# AFE_Channel_2.net
KiCad netlist of a schematic drawn in Altium Designer
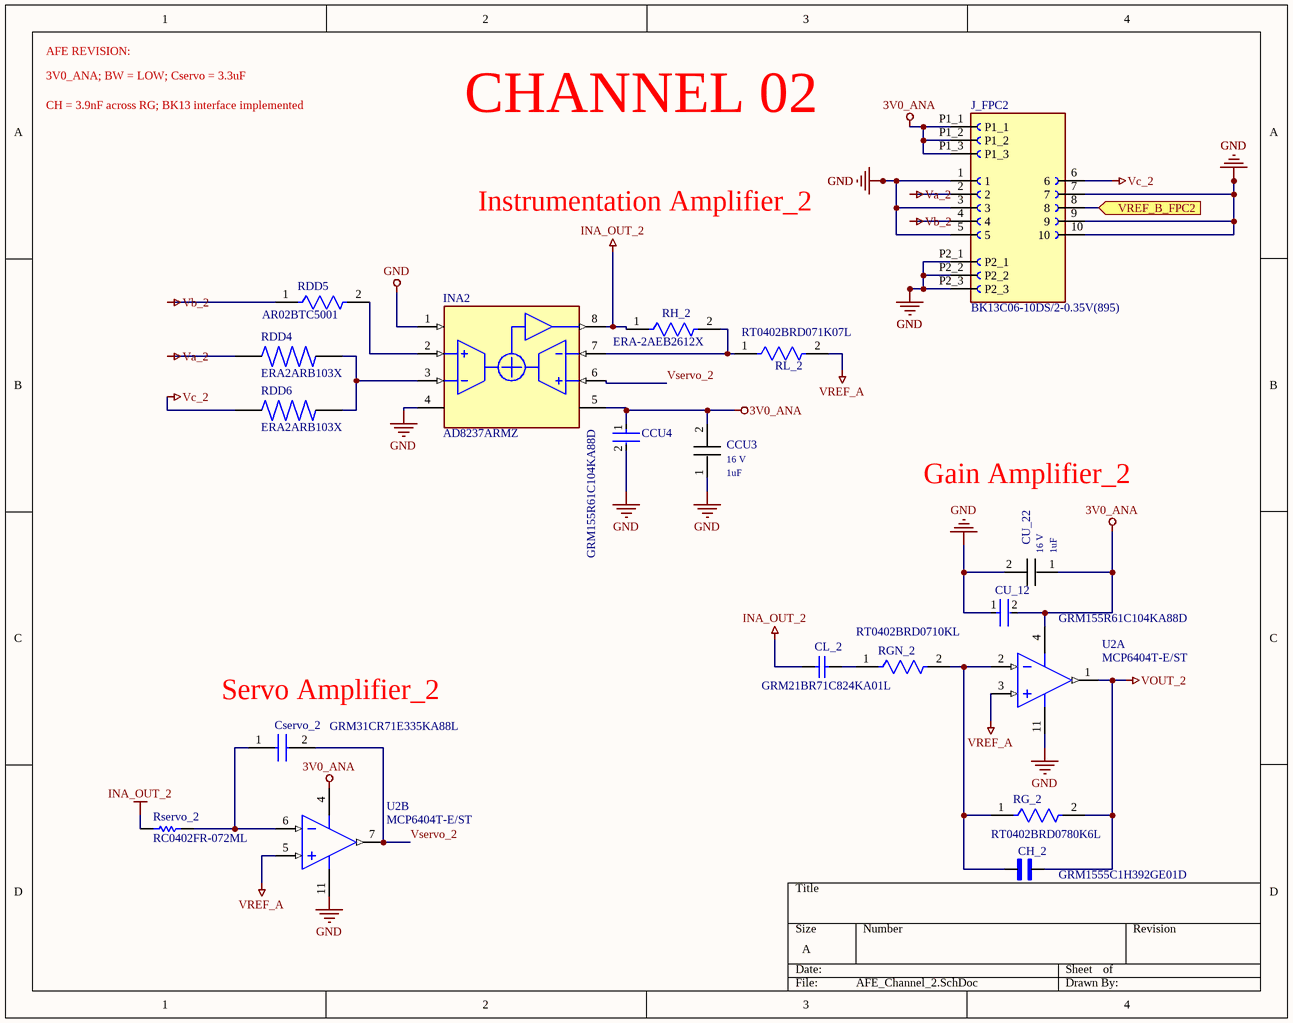
[diagram p0: AFE_Channel_2.SchDoc]

(export (version "E")
  (design (tool "Eeschema 10.0.6"))
  (components
    (comp (ref "CCU3")
      (value "MURATA_GRM155C71C105KE11D")
      (footprint "MURATA_GRM155C71C105KE11D_0:*MURATA_GRM155C71C105KE11D_0")
      (description "Murata GRM155C71C105KE11D: 1 uF 16 V X7S +/-10%, 0402/1005 metric")
      (fields (field (name "MF") "Murata") (field (name "MP") "GRM155C71C105KE11D"))
      (libsource (lib "EMG_Controlled_R5") (part "EMG_R5_CCU3"))
    )
    (comp (ref "CCU4")
      (value "GRM155R61C104KA88D")
      (footprint "96DF66F8-B997-472F-A885-42BCAAE661B2_FP-GRM155-0_05-IPC_C:FP-GRM155-0_05-IPC_C")
      (description "CAP CER 0.1UF 16V X5R 0402")
      (fields (field (name "VOLTAGE") "16V") (field (name "TOLERANCE") "10%"))
      (libsource (lib "EMG_Controlled_R5") (part "EMG_R5_CCU4"))
    )
    (comp (ref "CH_2")
      (value "GRM1555C1H392GE01D")
      (footprint "GRM1555C1H392GE01D_0:CAPC1005X55N")
      (description "SMD capacitor C0G(EIA) with capacitance 3900pF Tol.2%. Rated voltage 50Vdc 125C")
      (fields (field (name "MF") "Murata Electronics"))
      (libsource (lib "EMG_Controlled_R5") (part "EMG_R5_CH_2"))
    )
    (comp (ref "CL_2")
      (value "GRM21BR71C824KA01L")
      (footprint "987105EF-01FA-4198-A59F-44D3B68BB40E_CAPC2013X135X45ML10T25:CAPC2013X135X45ML10T25")
      (fields (field (name "MANUFACTURER") "Murata"))
      (libsource (lib "EMG_Controlled_R5") (part "EMG_R5_CL_2"))
    )
    (comp (ref "Cservo_2")
      (value "GRM31CR71E335KA88L")
      (footprint "SamacSys:GRM31x")
      (description "Capacitor")
      (fields
        (field (name "MOUSER PART NUMBER") "81-GRM31CR71E335KA8L")
        (field (name "MANUFACTURER") "Murata")
      )
      (libsource (lib "EMG_Controlled_R5") (part "EMG_R5_Cservo_2"))
    )
    (comp (ref "CU_12")
      (value "GRM155R61C104KA88D")
      (footprint "96DF66F8-B997-472F-A885-42BCAAE661B2_FP-GRM155-0_05-IPC_C:FP-GRM155-0_05-IPC_C")
      (description "CAP CER 0.1UF 16V X5R 0402")
      (fields (field (name "VOLTAGE") "16V") (field (name "TOLERANCE") "10%"))
      (libsource (lib "EMG_Controlled_R5") (part "EMG_R5_CU_12"))
    )
    (comp (ref "CU_22")
      (value "MURATA_GRM155C71C105KE11D")
      (footprint "MURATA_GRM155C71C105KE11D_0:*MURATA_GRM155C71C105KE11D_0")
      (description "Murata GRM155C71C105KE11D: 1 uF 16 V X7S +/-10%, 0402/1005 metric")
      (fields (field (name "MF") "Murata") (field (name "MP") "GRM155C71C105KE11D"))
      (libsource (lib "EMG_Controlled_R5") (part "EMG_R5_CU_22"))
    )
    (comp (ref "INA2")
      (value "AD8237ARMZ")
      (footprint "EMG_AD8237_R3:EMG_AD8237_R3_MSOP8")
      (description "Micropower, Zero Drift, True Rail-to-Rail Instrumentation Amplifier")
      (fields (field (name "MF") "Analog Devices"))
      (libsource (lib "EMG_Controlled_R5") (part "EMG_R5_INA2"))
    )
    (comp (ref "J_FPC2")
      (value "BK13C06-10DS/2-0.35V(895)")
      (footprint "BK13C06-10DS_2-0.35V_895__0:HIROSE_BK13C06-10DS/2-0.35V(895)")
      (description "10 Position Connector Receptacle, Center Strip Contacts Surface Mount Gold")
      (fields (field (name "MF") "Hirose Electric Co Ltd"))
      (libsource (lib "EMG_Controlled_R5") (part "EMG_R5_J_FPC2"))
    )
    (comp (ref "RDD4")
      (value "ERA2ARB103X")
      (footprint "ERA2ARB103X_0:RES_ERA2ARB103X")
      (libsource (lib "EMG_Controlled_R5") (part "EMG_R5_RDD4"))
    )
    (comp (ref "RDD5")
      (value "AR02BTC5001")
      (footprint "7D606042-220B-45EE-95DD-CA1A974E4C0D_FP-AC0402-MFG:FP-AC0402-MFG")
      (description "-55℃~+155℃ 50V 5kΩ 63mW Thin Film Resistor ±0.1% ±25ppm/℃ 0402 Chip Resistor - Surface Mount ROH")
      (fields
        (field (name "MANUFACTURER") "Viking Tech")
        (field (name "OCTOPART") "https://octopart.com/datasheet/viking-tech/AR02BTC5001")
      )
      (libsource (lib "EMG_Controlled_R5") (part "EMG_R5_RDD5"))
    )
    (comp (ref "RDD6")
      (value "ERA2ARB103X")
      (footprint "ERA2ARB103X_0:RES_ERA2ARB103X")
      (libsource (lib "EMG_Controlled_R5") (part "EMG_R5_RDD6"))
    )
    (comp (ref "RGN_2")
      (value "RT0402BRD0710KL")
      (footprint "B876F212-A29A-4983-9BB8-539D1BA2EBA1_FP-RT0402-MFG:FP-RT0402-MFG")
      (description "RES 10.0K OHM 1/16W .1% SMD 0402")
      (fields
        (field (name "MANUFACTURER") "Yageo")
        (field (name "OCTOPART") "https://octopart.com/rt0402brd0710kl-yageo-1181432")
      )
      (libsource (lib "EMG_Controlled_R5") (part "EMG_R5_RGN_2"))
    )
    (comp (ref "RG_2")
      (value "RT0402BRD0780K6L")
      (footprint "B876F212-A29A-4983-9BB8-539D1BA2EBA1_FP-RT0402-MFG:FP-RT0402-MFG")
      (description "RES SMD 80.6KOHM 0.1% 1/16W 0402")
      (fields
        (field (name "MANUFACTURER") "Yageo")
        (field (name "OCTOPART") "https://octopart.com/rt0402brd0780k6l-yageo-1468076")
      )
      (libsource (lib "EMG_Controlled_R5") (part "EMG_R5_RG_2"))
    )
    (comp (ref "RH_2")
      (value "ERA-2AEB2612X")
      (footprint "1CBBEC27-AD79-48E8-A701-2E235EA9F8F2_FP-AC0402-IPC_A:FP-AC0402-IPC_A")
      (description "RES 26.1kΩ ±0.1% 0.063W 0402")
      (fields (field (name "TOLERANCE") "0.1%") (field (name "MANUFACTURER") "PANASONIC"))
      (libsource (lib "EMG_Controlled_R5") (part "EMG_R5_RH_2"))
    )
    (comp (ref "RL_2")
      (value "RT0402BRD071K07L")
      (footprint "B876F212-A29A-4983-9BB8-539D1BA2EBA1_FP-RT0402-MFG:FP-RT0402-MFG")
      (description "RES SMD 1.07K OHM 0.1% 1/16W")
      (fields
        (field (name "OCTOPART") "https://octopart.com/rt0402brd071k07l-yageo-1400807")
        (field (name "MANUFACTURER") "Yageo")
      )
      (libsource (lib "EMG_Controlled_R5") (part "EMG_R5_RL_2"))
    )
    (comp (ref "Rservo_2")
      (value "RC0402FR-072ML")
      (footprint "3EB15388-1759-44FF-BAE1-1F0823F3E8F1_RESC1005X40X25NL05T10:RESC1005X40X25NL05T10")
      (fields (field (name "MANUFACTURER") "Yageo / Phycomp"))
      (libsource (lib "EMG_Controlled_R5") (part "EMG_R5_Rservo_2"))
    )
    (comp (ref "U2")
      (value "MCP6404T-E/ST")
      (footprint "CEF93338-31F0-4C64-85B6-F650E0BB75E3_TSSOP-ST14_N:TSSOP-ST14_N")
      (description "None")
      (libsource (lib "EMG_Controlled_R5") (part "EMG_R5_U2"))
    )
  )
  (nets
    (net (code "1") (name "/VREF_B_FPC2") (class "Default")
      (node (ref "J_FPC2") (pin "8") (pinfunction "8_8") (pintype "passive"))
    )
    (net (code "2") (name "/Vservo_2") (class "Default")
      (node (ref "Cservo_2") (pin "2") (pinfunction "2_2") (pintype "passive"))
      (node (ref "INA2") (pin "6") (pinfunction "REF_6") (pintype "input"))
      (node (ref "U2") (pin "7") (pinfunction "VOUTB_7") (pintype "output"))
    )
    (net (code "3") (name "3V0_ANA") (class "Default")
      (node (ref "CCU3") (pin "2") (pinfunction "2_2") (pintype "passive"))
      (node (ref "CCU4") (pin "1") (pinfunction "1_1") (pintype "passive"))
      (node (ref "CU_12") (pin "2") (pinfunction "2_2") (pintype "passive"))
      (node (ref "CU_22") (pin "1") (pinfunction "1_1") (pintype "passive"))
      (node (ref "INA2") (pin "5") (pinfunction "+VS_5") (pintype "power_in"))
      (node (ref "J_FPC2") (pin "P1_1") (pinfunction "P1_1_P1_1") (pintype "power_in"))
      (node (ref "J_FPC2") (pin "P1_2") (pinfunction "P1_2_P1_2") (pintype "power_in"))
      (node (ref "J_FPC2") (pin "P1_3") (pinfunction "P1_3_P1_3") (pintype "power_in"))
      (node (ref "U2") (pin "4") (pinfunction "VDD_4") (pintype "power_in"))
    )
    (net (code "4") (name "GND") (class "Default")
      (node (ref "CCU3") (pin "1") (pinfunction "1_1") (pintype "passive"))
      (node (ref "CCU4") (pin "2") (pinfunction "2_2") (pintype "passive"))
      (node (ref "CU_12") (pin "1") (pinfunction "1_1") (pintype "passive"))
      (node (ref "CU_22") (pin "2") (pinfunction "2_2") (pintype "passive"))
      (node (ref "INA2") (pin "1") (pinfunction "BW_1") (pintype "input"))
      (node (ref "INA2") (pin "4") (pinfunction "-VS_4") (pintype "power_in"))
      (node (ref "J_FPC2") (pin "1") (pinfunction "1_1") (pintype "passive"))
      (node (ref "J_FPC2") (pin "10") (pinfunction "10_10") (pintype "passive"))
      (node (ref "J_FPC2") (pin "3") (pinfunction "3_3") (pintype "passive"))
      (node (ref "J_FPC2") (pin "5") (pinfunction "5_5") (pintype "passive"))
      (node (ref "J_FPC2") (pin "7") (pinfunction "7_7") (pintype "passive"))
      (node (ref "J_FPC2") (pin "9") (pinfunction "9_9") (pintype "passive"))
      (node (ref "J_FPC2") (pin "P2_1") (pinfunction "P2_1_P2_1") (pintype "power_in"))
      (node (ref "J_FPC2") (pin "P2_2") (pinfunction "P2_2_P2_2") (pintype "power_in"))
      (node (ref "J_FPC2") (pin "P2_3") (pinfunction "P2_3_P2_3") (pintype "power_in"))
      (node (ref "U2") (pin "11") (pinfunction "VSS_11") (pintype "power_in"))
    )
    (net (code "5") (name "INA_OUT_2") (class "Default")
      (node (ref "CL_2") (pin "2") (pinfunction "2_2") (pintype "passive"))
      (node (ref "INA2") (pin "8") (pinfunction "VOUT_8") (pintype "output"))
      (node (ref "RH_2") (pin "1") (pinfunction "1_1") (pintype "passive"))
      (node (ref "Rservo_2") (pin "2") (pinfunction "2_2") (pintype "passive"))
    )
    (net (code "6") (name "Net-(CL_2-Pad1)") (class "Default")
      (node (ref "CL_2") (pin "1") (pinfunction "1_1") (pintype "passive"))
      (node (ref "RGN_2") (pin "1") (pinfunction "1_1") (pintype "passive"))
    )
    (net (code "7") (name "Net-(INA2-+IN)") (class "Default")
      (node (ref "INA2") (pin "2") (pinfunction "+IN_2") (pintype "input"))
      (node (ref "RDD5") (pin "2") (pinfunction "2_2") (pintype "passive"))
    )
    (net (code "8") (name "Net-(INA2--IN)") (class "Default")
      (node (ref "INA2") (pin "3") (pinfunction "-IN_3") (pintype "input"))
      (node (ref "RDD4") (pin "2") (pinfunction "2_2") (pintype "passive"))
      (node (ref "RDD6") (pin "2") (pinfunction "2_2") (pintype "passive"))
    )
    (net (code "9") (name "Net-(INA2-FB)") (class "Default")
      (node (ref "INA2") (pin "7") (pinfunction "FB_7") (pintype "input"))
      (node (ref "RH_2") (pin "2") (pinfunction "2_2") (pintype "passive"))
      (node (ref "RL_2") (pin "1") (pinfunction "1_1") (pintype "passive"))
    )
    (net (code "10") (name "Net-(U2A-VINA-)") (class "Default")
      (node (ref "CH_2") (pin "2") (pinfunction "2_2") (pintype "passive"))
      (node (ref "RGN_2") (pin "2") (pinfunction "2_2") (pintype "passive"))
      (node (ref "RG_2") (pin "1") (pinfunction "1_1") (pintype "passive"))
      (node (ref "U2") (pin "2") (pinfunction "VINA-_2") (pintype "input"))
    )
    (net (code "11") (name "Net-(U2B-VINB-)") (class "Default")
      (node (ref "Cservo_2") (pin "1") (pinfunction "1_1") (pintype "passive"))
      (node (ref "Rservo_2") (pin "1") (pinfunction "1_1") (pintype "passive"))
      (node (ref "U2") (pin "6") (pinfunction "VINB-_6") (pintype "input"))
    )
    (net (code "12") (name "VOUT_2") (class "Default")
      (node (ref "CH_2") (pin "1") (pinfunction "1_1") (pintype "passive"))
      (node (ref "RG_2") (pin "2") (pinfunction "2_2") (pintype "passive"))
      (node (ref "U2") (pin "1") (pinfunction "VOUTA_1") (pintype "output"))
    )
    (net (code "13") (name "VREF_A") (class "Default")
      (node (ref "RL_2") (pin "2") (pinfunction "2_2") (pintype "passive"))
      (node (ref "U2") (pin "3") (pinfunction "VINA+_3") (pintype "input"))
      (node (ref "U2") (pin "5") (pinfunction "VINB+_5") (pintype "input"))
    )
    (net (code "14") (name "Va_2") (class "Default")
      (node (ref "J_FPC2") (pin "2") (pinfunction "2_2") (pintype "passive"))
      (node (ref "RDD4") (pin "1") (pinfunction "1_1") (pintype "passive"))
    )
    (net (code "15") (name "Vb_2") (class "Default")
      (node (ref "J_FPC2") (pin "4") (pinfunction "4_4") (pintype "passive"))
      (node (ref "RDD5") (pin "1") (pinfunction "1_1") (pintype "passive"))
    )
    (net (code "16") (name "Vc_2") (class "Default")
      (node (ref "J_FPC2") (pin "6") (pinfunction "6_6") (pintype "passive"))
      (node (ref "RDD6") (pin "1") (pinfunction "1_1") (pintype "passive"))
    )
  )
)
